# 50Hz.net
KiCad netlist of a schematic drawn in Altium Designer
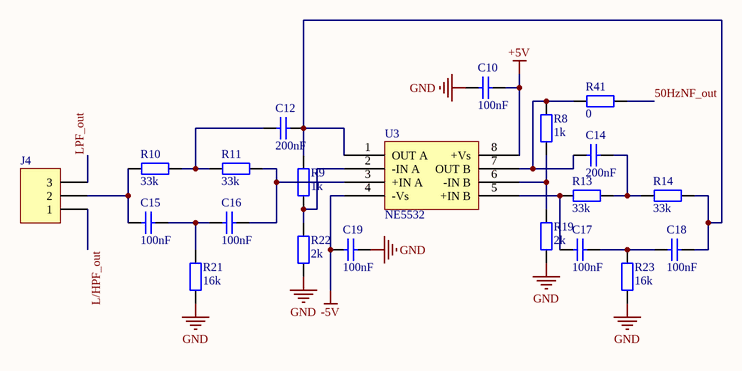
[diagram p0: 50Hz陷波器（两次陷波）.SchDoc]

(export (version "E")
  (design (tool "Eeschema 10.0.6"))
  (components
    (comp (ref "C10")
      (value "100nF")
      (footprint "LC-0805_C")
      (description "100nF��0805��50V,+/-10%")
      (libsource (lib "ECG") (part "Cap"))
    )
    (comp (ref "C12")
      (value "200nF")
      (footprint "LC-0805_C")
      (description "100nF��0805��50V,+/-10%")
      (libsource (lib "ECG") (part "Cap"))
    )
    (comp (ref "C14")
      (value "200nF")
      (footprint "LC-0805_C")
      (description "100nF��0805��50V,+/-10%")
      (libsource (lib "ECG") (part "Cap"))
    )
    (comp (ref "C15")
      (value "100nF")
      (footprint "LC-0805_C")
      (description "100nF��0805��50V,+/-10%")
      (libsource (lib "ECG") (part "Cap"))
    )
    (comp (ref "C16")
      (value "100nF")
      (footprint "LC-0805_C")
      (description "100nF��0805��50V,+/-10%")
      (libsource (lib "ECG") (part "Cap"))
    )
    (comp (ref "C17")
      (value "100nF")
      (footprint "LC-0805_C")
      (description "100nF��0805��50V,+/-10%")
      (libsource (lib "ECG") (part "Cap"))
    )
    (comp (ref "C18")
      (value "100nF")
      (footprint "LC-0805_C")
      (description "100nF��0805��50V,+/-10%")
      (libsource (lib "ECG") (part "Cap"))
    )
    (comp (ref "C19")
      (value "100nF")
      (footprint "LC-0805_C")
      (description "100nF��0805��50V,+/-10%")
      (libsource (lib "ECG") (part "Cap"))
    )
    (comp (ref "J4")
      (value "������")
      (footprint "HDR1X3")
      (description "1*3Pin,2.54mm��൥����")
      (fields (field (name "PUBLISHER") "Altium Limited"))
      (libsource (lib "ECG") (part "Header 3"))
    )
    (comp (ref "R8")
      (value "1k")
      (footprint "LC-0805_R")
      (description "10k��,0805,��5%")
      (libsource (lib "ECG") (part "R"))
    )
    (comp (ref "R9")
      (value "1k")
      (footprint "LC-0805_R")
      (description "10k��,0805,��5%")
      (libsource (lib "ECG") (part "R"))
    )
    (comp (ref "R10")
      (value "33k")
      (footprint "LC-0805_R")
      (description "10k��,0805,��5%")
      (libsource (lib "ECG") (part "R"))
    )
    (comp (ref "R11")
      (value "33k")
      (footprint "LC-0805_R")
      (description "10k��,0805,��5%")
      (libsource (lib "ECG") (part "R"))
    )
    (comp (ref "R13")
      (value "33k")
      (footprint "LC-0805_R")
      (description "10k��,0805,��5%")
      (libsource (lib "ECG") (part "R"))
    )
    (comp (ref "R14")
      (value "33k")
      (footprint "LC-0805_R")
      (description "10k��,0805,��5%")
      (libsource (lib "ECG") (part "R"))
    )
    (comp (ref "R19")
      (value "2k")
      (footprint "LC-0805_R")
      (description "10k��,0805,��5%")
      (libsource (lib "ECG") (part "R"))
    )
    (comp (ref "R21")
      (value "16k")
      (footprint "LC-0805_R")
      (description "10k��,0805,��5%")
      (libsource (lib "ECG") (part "R"))
    )
    (comp (ref "R22")
      (value "2k")
      (footprint "LC-0805_R")
      (description "10k��,0805,��5%")
      (libsource (lib "ECG") (part "R"))
    )
    (comp (ref "R23")
      (value "16k")
      (footprint "LC-0805_R")
      (description "10k��,0805,��5%")
      (libsource (lib "ECG") (part "R"))
    )
    (comp (ref "R41")
      (value "0")
      (footprint "LC-0805_R")
      (description "10k��,0805,��5%")
      (libsource (lib "ECG") (part "R"))
    )
    (comp (ref "U3")
      (value "NE5532")
      (footprint "DIP-8")
      (description "NE5532��SO-8")
      (libsource (lib "ECG") (part "NE5532"))
    )
  )
  (nets
    (net (code "1") (name "+5V") (class "Default")
      (node (ref "C10") (pin "1") (pinfunction "1_1") (pintype "passive"))
      (node (ref "U3") (pin "8") (pinfunction "+Vs_8") (pintype "passive"))
    )
    (net (code "2") (name "-5V") (class "Default")
      (node (ref "C19") (pin "2") (pinfunction "2_2") (pintype "passive"))
      (node (ref "U3") (pin "4") (pinfunction "-Vs_4") (pintype "passive"))
    )
    (net (code "3") (name "/50HzNF_out") (class "Default") (node (ref "R41") (pin "2") (pintype "passive")))
    (net (code "4") (name "/LPF_out") (class "Default")
      (node (ref "J4") (pin "3") (pinfunction "3_3") (pintype "passive"))
    )
    (net (code "5") (name "/L{slash}HPF_out") (class "Default")
      (node (ref "J4") (pin "1") (pinfunction "1_1") (pintype "passive"))
    )
    (net (code "6") (name "GND") (class "Default")
      (node (ref "C10") (pin "2") (pinfunction "2_2") (pintype "passive"))
      (node (ref "C19") (pin "1") (pinfunction "1_1") (pintype "passive"))
      (node (ref "R19") (pin "1") (pintype "passive"))
      (node (ref "R21") (pin "1") (pintype "passive"))
      (node (ref "R22") (pin "1") (pintype "passive"))
      (node (ref "R23") (pin "1") (pintype "passive"))
    )
    (net (code "7") (name "Net-(C12-Pad2)") (class "Default")
      (node (ref "C12") (pin "2") (pinfunction "2_2") (pintype "passive"))
      (node (ref "R10") (pin "2") (pintype "passive"))
      (node (ref "R11") (pin "1") (pintype "passive"))
    )
    (net (code "8") (name "Net-(C14-Pad1)") (class "Default")
      (node (ref "C14") (pin "1") (pinfunction "1_1") (pintype "passive"))
      (node (ref "R13") (pin "2") (pintype "passive"))
      (node (ref "R14") (pin "1") (pintype "passive"))
    )
    (net (code "9") (name "Net-(C15-Pad1)") (class "Default")
      (node (ref "C15") (pin "1") (pinfunction "1_1") (pintype "passive"))
      (node (ref "C16") (pin "2") (pinfunction "2_2") (pintype "passive"))
      (node (ref "R21") (pin "2") (pintype "passive"))
    )
    (net (code "10") (name "Net-(C15-Pad2)") (class "Default")
      (node (ref "C15") (pin "2") (pinfunction "2_2") (pintype "passive"))
      (node (ref "J4") (pin "2") (pinfunction "2_2") (pintype "passive"))
      (node (ref "R10") (pin "1") (pintype "passive"))
    )
    (net (code "11") (name "Net-(C17-Pad1)") (class "Default")
      (node (ref "C17") (pin "1") (pinfunction "1_1") (pintype "passive"))
      (node (ref "C18") (pin "2") (pinfunction "2_2") (pintype "passive"))
      (node (ref "R23") (pin "2") (pintype "passive"))
    )
    (net (code "12") (name "Net-(U3-+IN_A)") (class "Default")
      (node (ref "C16") (pin "1") (pinfunction "1_1") (pintype "passive"))
      (node (ref "R11") (pin "2") (pintype "passive"))
      (node (ref "U3") (pin "3") (pinfunction "+IN_A_3") (pintype "passive"))
    )
    (net (code "13") (name "Net-(U3-+IN_B)") (class "Default")
      (node (ref "C17") (pin "2") (pinfunction "2_2") (pintype "passive"))
      (node (ref "R13") (pin "1") (pintype "passive"))
      (node (ref "U3") (pin "5") (pinfunction "+IN_B_5") (pintype "passive"))
    )
    (net (code "14") (name "Net-(U3--IN_A)") (class "Default")
      (node (ref "R22") (pin "2") (pintype "passive"))
      (node (ref "R9") (pin "1") (pintype "passive"))
      (node (ref "U3") (pin "2") (pinfunction "-IN_A_2") (pintype "passive"))
    )
    (net (code "15") (name "Net-(U3--IN_B)") (class "Default")
      (node (ref "R19") (pin "2") (pintype "passive"))
      (node (ref "R8") (pin "1") (pintype "passive"))
      (node (ref "U3") (pin "6") (pinfunction "-IN_B_6") (pintype "passive"))
    )
    (net (code "16") (name "Net-(U3-OUT_A)") (class "Default")
      (node (ref "C12") (pin "1") (pinfunction "1_1") (pintype "passive"))
      (node (ref "C18") (pin "1") (pinfunction "1_1") (pintype "passive"))
      (node (ref "R14") (pin "2") (pintype "passive"))
      (node (ref "R9") (pin "2") (pintype "passive"))
      (node (ref "U3") (pin "1") (pinfunction "OUT_A_1") (pintype "passive"))
    )
    (net (code "17") (name "Net-(U3-OUT_B)") (class "Default")
      (node (ref "C14") (pin "2") (pinfunction "2_2") (pintype "passive"))
      (node (ref "R41") (pin "1") (pintype "passive"))
      (node (ref "R8") (pin "2") (pintype "passive"))
      (node (ref "U3") (pin "7") (pinfunction "OUT_B_7") (pintype "passive"))
    )
  )
)
